# sheet.net
KiCad netlist of a schematic drawn in EasyEDA
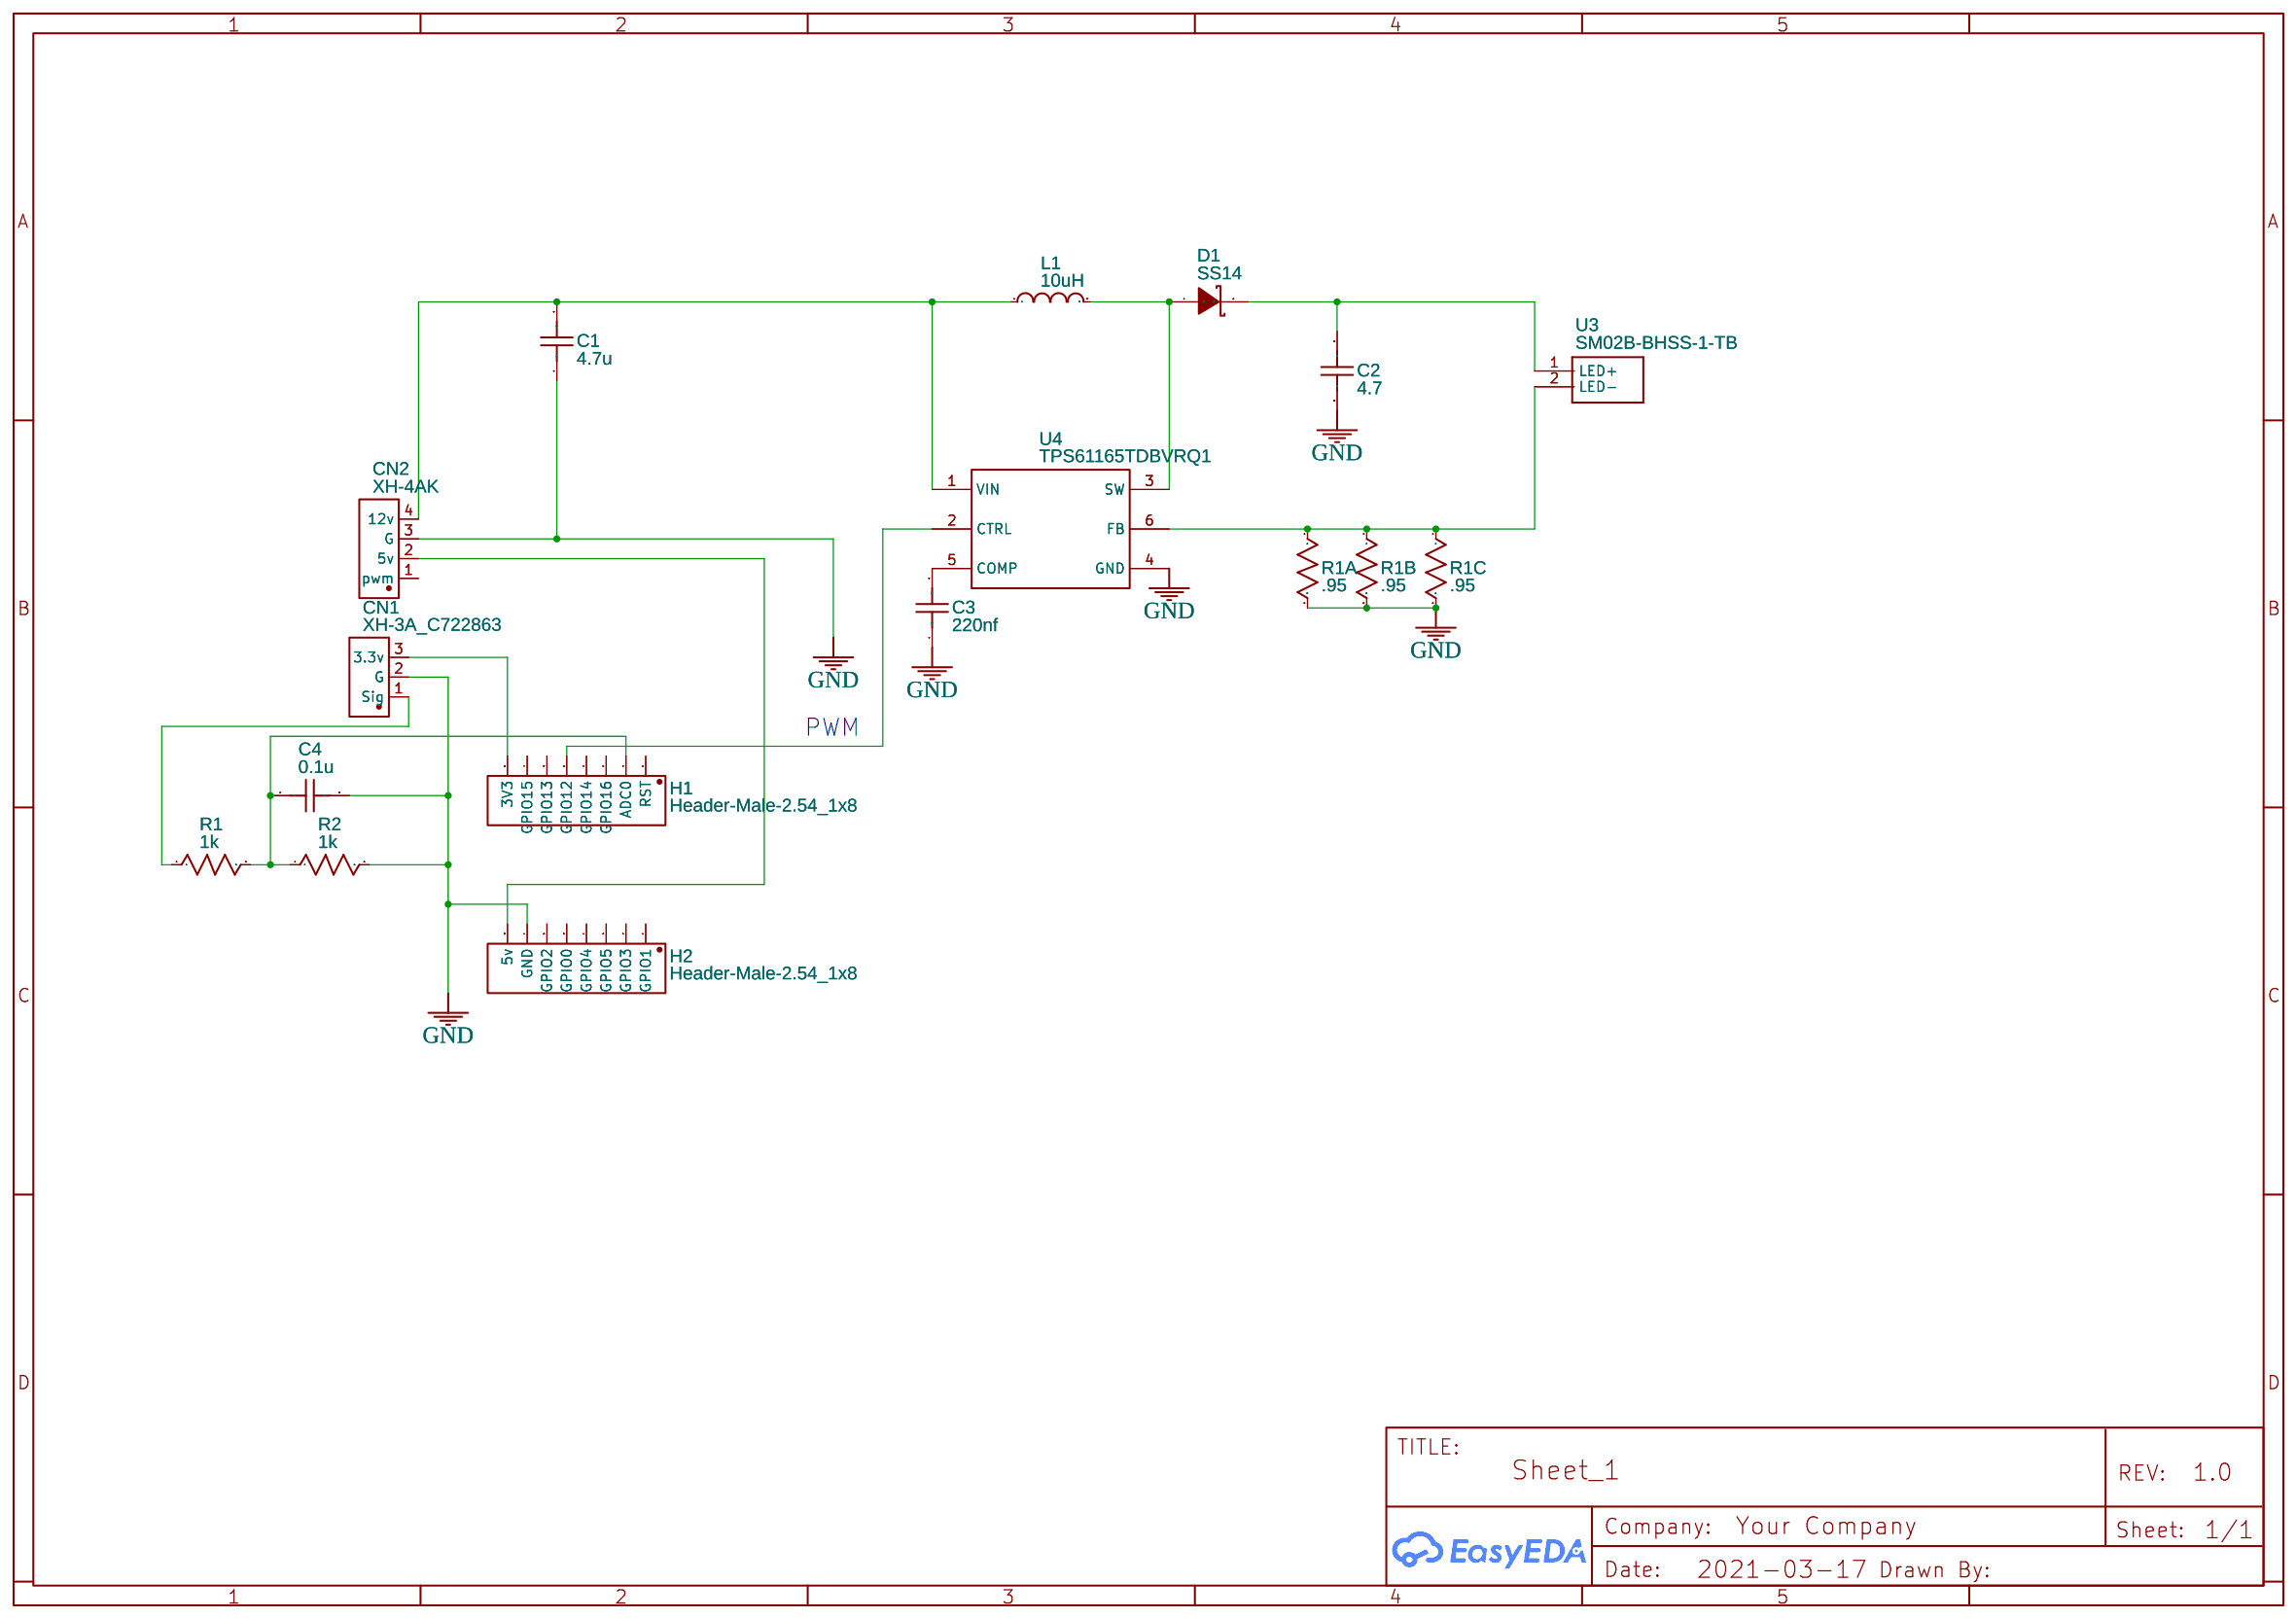
[diagram p0: schematic sheet]

(export (version "E")
  (design (tool "Eeschema 10.0.6"))
  (components
    (comp (ref "C1") (value "4.7u") (libsource (lib "") (part "C_0603_US")))
    (comp (ref "C2") (value "4.7") (libsource (lib "") (part "C_0603_US_1")))
    (comp (ref "C3") (value "220nf") (libsource (lib "") (part "C_0603_US")))
    (comp (ref "C4") (value "0.1u") (libsource (lib "") (part "C_0603_US_2")))
    (comp (ref "CN1")
      (value "XH-3A_C722863")
      (fields (field (name "BOM_Manufacturer Part") "XH-3A") (field (name "BOM_Supplier Part") "C722863"))
      (libsource (lib "") (part "XH-3A_C722863"))
    )
    (comp (ref "CN2")
      (value "XH-4AK")
      (fields (field (name "BOM_Supplier Part") "C722871"))
      (libsource (lib "") (part "XH-4AK"))
    )
    (comp (ref "D1")
      (value "SS14")
      (fields (field (name "BOM_Supplier Part") "C2480"))
      (libsource (lib "") (part "SS14"))
    )
    (comp (ref "H1")
      (value "Header-Male-2.54_1x8")
      (fields
        (field (name "BOM_Manufacturer Part") "210S-1*8P L=11.6MMGold-plated black")
        (field (name "BOM_Supplier Part") "C124381")
      )
      (libsource (lib "") (part "Header-Male-2.54_1x8_1"))
    )
    (comp (ref "H2")
      (value "Header-Male-2.54_1x8")
      (fields
        (field (name "BOM_Manufacturer Part") "210S-1*8P L=11.6MMGold-plated black")
        (field (name "BOM_Supplier Part") "C124381")
      )
      (libsource (lib "") (part "Header-Male-2.54_1x8"))
    )
    (comp (ref "L1")
      (value "10uH")
      (fields
        (field (name "BOM_Manufacturer Part") "VLCF5020T-100M1R1-1")
        (field (name "BOM_Supplier Part") "C89448")
      )
      (libsource (lib "") (part "VLCF5020T-100M1R1-1"))
    )
    (comp (ref "R1") (value "1k") (libsource (lib "") (part "R_0603_US")))
    (comp (ref "R1A") (value ".95") (libsource (lib "") (part "R_0603_US_1")))
    (comp (ref "R1B") (value ".95") (libsource (lib "") (part "R_0603_US_3")))
    (comp (ref "R1C") (value ".95") (libsource (lib "") (part "R_0603_US_2")))
    (comp (ref "R2") (value "1k") (libsource (lib "") (part "R_0603_US")))
    (comp (ref "U3") (value "SM02B-BHSS-1-TB") (libsource (lib "") (part "SM02B-BHSS-1-TB")))
    (comp (ref "U4") (value "TPS61165TDBVRQ1") (libsource (lib "") (part "TPS61165TDBVRQ1")))
  )
  (nets
    (net (code "1") (name "GND") (class "Default")
      (node (ref "C1") (pin "1") (pinfunction "1_1") (pintype "unspecified"))
      (node (ref "C2") (pin "2") (pinfunction "2_2") (pintype "unspecified"))
      (node (ref "C3") (pin "1") (pinfunction "1_1") (pintype "unspecified"))
      (node (ref "C4") (pin "2") (pinfunction "2_2") (pintype "unspecified"))
      (node (ref "CN1") (pin "2") (pinfunction "G_2") (pintype "unspecified"))
      (node (ref "CN2") (pin "3") (pinfunction "G_3") (pintype "unspecified"))
      (node (ref "H2") (pin "7") (pinfunction "GND_7") (pintype "unspecified"))
      (node (ref "R1A") (pin "2") (pinfunction "2_2") (pintype "unspecified"))
      (node (ref "R1B") (pin "2") (pinfunction "2_2") (pintype "unspecified"))
      (node (ref "R1C") (pin "2") (pinfunction "2_2") (pintype "unspecified"))
      (node (ref "R2") (pin "2") (pinfunction "2_2") (pintype "unspecified"))
      (node (ref "U4") (pin "4") (pinfunction "GND_4") (pintype "passive"))
    )
    (net (code "2") (name "Net-(CN1-3.3v)") (class "Default")
      (node (ref "CN1") (pin "3") (pinfunction "3.3v_3") (pintype "unspecified"))
      (node (ref "H1") (pin "8") (pinfunction "3V3_8") (pintype "unspecified"))
    )
    (net (code "3") (name "Net-(CN1-Sig)") (class "Default")
      (node (ref "CN1") (pin "1") (pinfunction "Sig_1") (pintype "unspecified"))
      (node (ref "R1") (pin "1") (pinfunction "1_1") (pintype "unspecified"))
    )
    (net (code "4") (name "Net-(CN2-5v)") (class "Default")
      (node (ref "CN2") (pin "2") (pinfunction "5v_2") (pintype "unspecified"))
      (node (ref "H2") (pin "8") (pinfunction "5v_8") (pintype "unspecified"))
    )
    (net (code "5") (name "Net-(CN2-12v)") (class "Default")
      (node (ref "C1") (pin "2") (pinfunction "2_2") (pintype "unspecified"))
      (node (ref "CN2") (pin "4") (pinfunction "12v_4") (pintype "unspecified"))
      (node (ref "L1") (pin "1") (pinfunction "1_1") (pintype "unspecified"))
      (node (ref "U4") (pin "1") (pinfunction "VIN_1") (pintype "passive"))
    )
    (net (code "6") (name "Net-(D1-A)") (class "Default")
      (node (ref "D1") (pin "1") (pinfunction "A_1") (pintype "unspecified"))
      (node (ref "L1") (pin "2") (pinfunction "2_2") (pintype "unspecified"))
      (node (ref "U4") (pin "3") (pinfunction "SW_3") (pintype "passive"))
    )
    (net (code "7") (name "Net-(D1-K)") (class "Default")
      (node (ref "C2") (pin "1") (pinfunction "1_1") (pintype "unspecified"))
      (node (ref "D1") (pin "2") (pinfunction "K_2") (pintype "unspecified"))
      (node (ref "U3") (pin "1") (pinfunction "LED+_1") (pintype "bidirectional"))
    )
    (net (code "8") (name "Net-(H1-ADC0)") (class "Default")
      (node (ref "C4") (pin "1") (pinfunction "1_1") (pintype "unspecified"))
      (node (ref "H1") (pin "2") (pinfunction "ADC0_2") (pintype "unspecified"))
      (node (ref "R1") (pin "2") (pinfunction "2_2") (pintype "unspecified"))
      (node (ref "R2") (pin "1") (pinfunction "1_1") (pintype "unspecified"))
    )
    (net (code "9") (name "Net-(H1-GPIO12)") (class "Default")
      (node (ref "H1") (pin "5") (pinfunction "GPIO12_5") (pintype "unspecified"))
      (node (ref "U4") (pin "2") (pinfunction "CTRL_2") (pintype "unspecified"))
    )
    (net (code "10") (name "Net-(U3-LED-)") (class "Default")
      (node (ref "R1A") (pin "1") (pinfunction "1_1") (pintype "unspecified"))
      (node (ref "R1B") (pin "1") (pinfunction "1_1") (pintype "unspecified"))
      (node (ref "R1C") (pin "1") (pinfunction "1_1") (pintype "unspecified"))
      (node (ref "U3") (pin "2") (pinfunction "LED-_2") (pintype "bidirectional"))
      (node (ref "U4") (pin "6") (pinfunction "FB_6") (pintype "unspecified"))
    )
    (net (code "11") (name "Net-(U4-COMP)") (class "Default")
      (node (ref "C3") (pin "2") (pinfunction "2_2") (pintype "unspecified"))
      (node (ref "U4") (pin "5") (pinfunction "COMP_5") (pintype "unspecified"))
    )
    (net (code "12") (name "unconnected-(CN2-pwm-Pad1)") (class "Default")
      (node (ref "CN2") (pin "1") (pinfunction "pwm_1") (pintype "unspecified"))
    )
    (net (code "13") (name "unconnected-(H1-GPIO13-Pad6)") (class "Default")
      (node (ref "H1") (pin "6") (pinfunction "GPIO13_6") (pintype "unspecified"))
    )
    (net (code "14") (name "unconnected-(H1-GPIO14-Pad4)") (class "Default")
      (node (ref "H1") (pin "4") (pinfunction "GPIO14_4") (pintype "unspecified"))
    )
    (net (code "15") (name "unconnected-(H1-GPIO15-Pad7)") (class "Default")
      (node (ref "H1") (pin "7") (pinfunction "GPIO15_7") (pintype "unspecified"))
    )
    (net (code "16") (name "unconnected-(H1-GPIO16-Pad3)") (class "Default")
      (node (ref "H1") (pin "3") (pinfunction "GPIO16_3") (pintype "unspecified"))
    )
    (net (code "17") (name "unconnected-(H1-RST-Pad1)") (class "Default")
      (node (ref "H1") (pin "1") (pinfunction "RST_1") (pintype "unspecified"))
    )
    (net (code "18") (name "unconnected-(H2-GPIO0-Pad5)") (class "Default")
      (node (ref "H2") (pin "5") (pinfunction "GPIO0_5") (pintype "unspecified"))
    )
    (net (code "19") (name "unconnected-(H2-GPIO1-Pad1)") (class "Default")
      (node (ref "H2") (pin "1") (pinfunction "GPIO1_1") (pintype "unspecified"))
    )
    (net (code "20") (name "unconnected-(H2-GPIO2-Pad6)") (class "Default")
      (node (ref "H2") (pin "6") (pinfunction "GPIO2_6") (pintype "unspecified"))
    )
    (net (code "21") (name "unconnected-(H2-GPIO3-Pad2)") (class "Default")
      (node (ref "H2") (pin "2") (pinfunction "GPIO3_2") (pintype "unspecified"))
    )
    (net (code "22") (name "unconnected-(H2-GPIO4-Pad4)") (class "Default")
      (node (ref "H2") (pin "4") (pinfunction "GPIO4_4") (pintype "unspecified"))
    )
    (net (code "23") (name "unconnected-(H2-GPIO5-Pad3)") (class "Default")
      (node (ref "H2") (pin "3") (pinfunction "GPIO5_3") (pintype "unspecified"))
    )
  )
)
